# BNSK_Authoring_Light.net
KiCad netlist of a schematic drawn in EAGLE
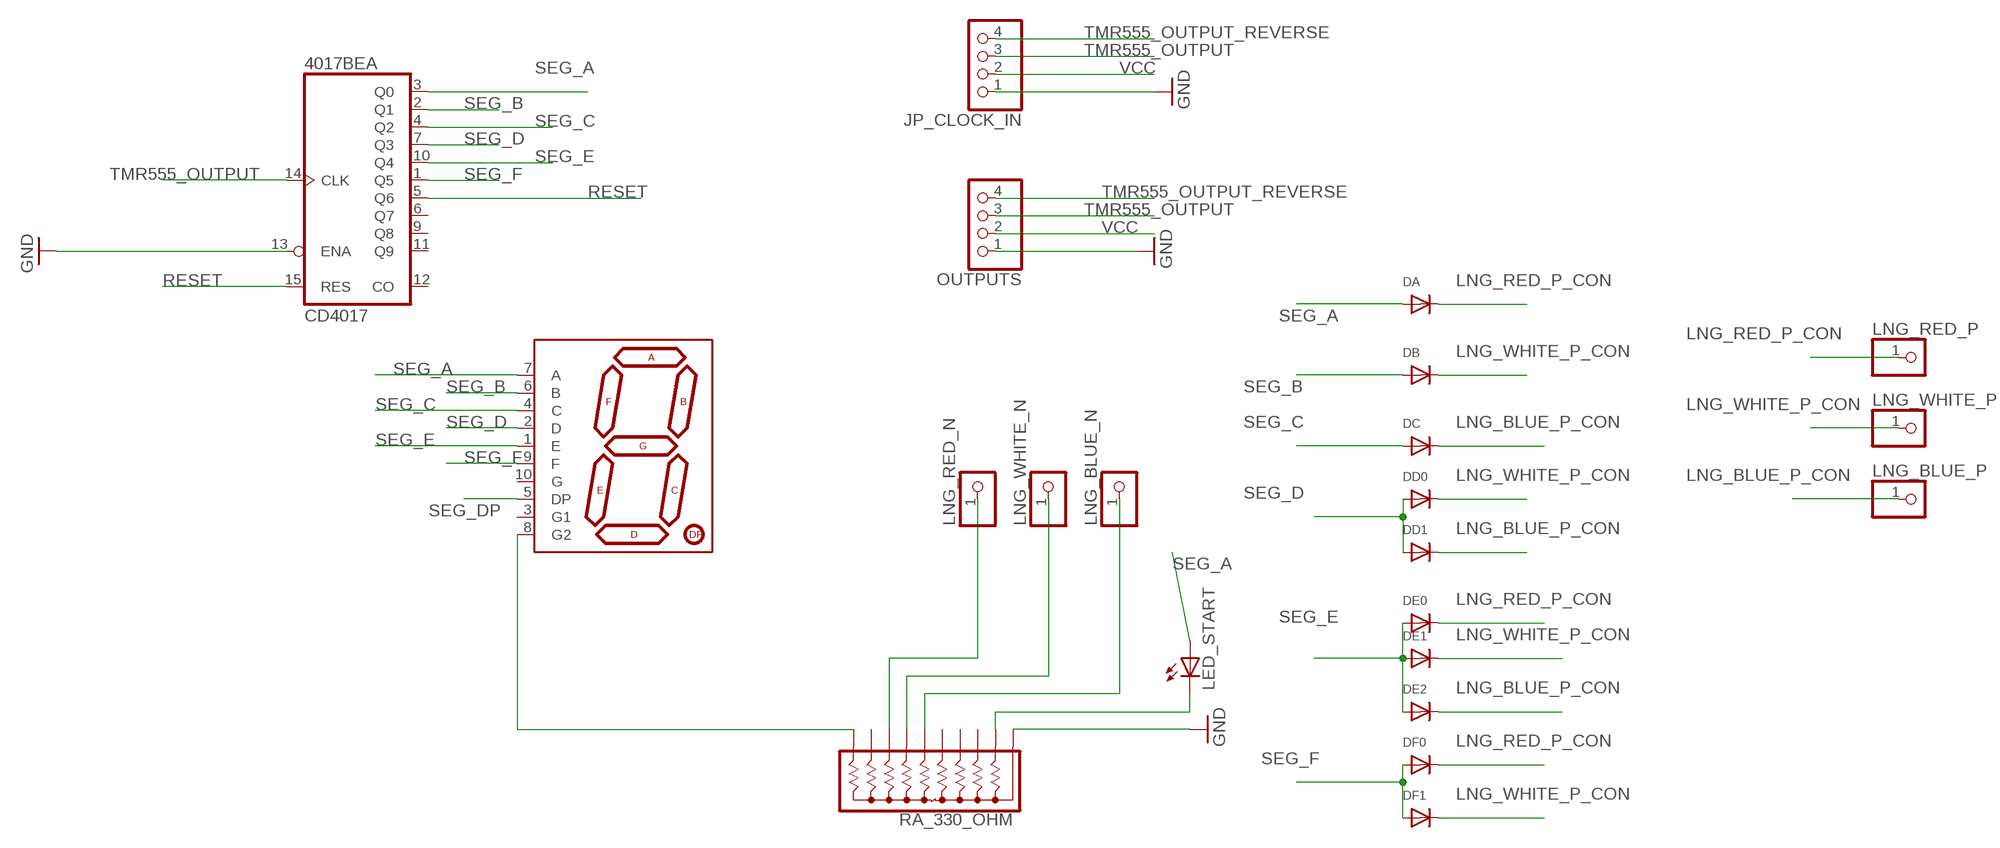
[diagram p0: schematic, sheet 1]

(export (version "E")
  (design (tool "Eeschema 10.0.6"))
  (components
    (comp (ref "4017BE")
      (value "CD4017")
      (footprint "eagle-import:DIL16")
      (libsource (lib "eagle-import") (part "CD4017"))
    )
    (comp (ref "DA")
      (value "DIODESMA")
      (footprint "eagle-import:SMADIODE")
      (libsource (lib "eagle-import") (part "DIODESMA"))
    )
    (comp (ref "DB")
      (value "DIODESMA")
      (footprint "eagle-import:SMADIODE")
      (libsource (lib "eagle-import") (part "DIODESMA"))
    )
    (comp (ref "DC")
      (value "DIODESMA")
      (footprint "eagle-import:SMADIODE")
      (libsource (lib "eagle-import") (part "DIODESMA"))
    )
    (comp (ref "DD0")
      (value "DIODESMA")
      (footprint "eagle-import:SMADIODE")
      (libsource (lib "eagle-import") (part "DIODESMA"))
    )
    (comp (ref "DD1")
      (value "DIODESMA")
      (footprint "eagle-import:SMADIODE")
      (libsource (lib "eagle-import") (part "DIODESMA"))
    )
    (comp (ref "DE0")
      (value "DIODESMA")
      (footprint "eagle-import:SMADIODE")
      (libsource (lib "eagle-import") (part "DIODESMA"))
    )
    (comp (ref "DE1")
      (value "DIODESMA")
      (footprint "eagle-import:SMADIODE")
      (libsource (lib "eagle-import") (part "DIODESMA"))
    )
    (comp (ref "DE2")
      (value "DIODESMA")
      (footprint "eagle-import:SMADIODE")
      (libsource (lib "eagle-import") (part "DIODESMA"))
    )
    (comp (ref "DF0")
      (value "DIODESMA")
      (footprint "eagle-import:SMADIODE")
      (libsource (lib "eagle-import") (part "DIODESMA"))
    )
    (comp (ref "DF1")
      (value "DIODESMA")
      (footprint "eagle-import:SMADIODE")
      (libsource (lib "eagle-import") (part "DIODESMA"))
    )
    (comp (ref "JP_CLOCK_IN")
      (value "PINHD-1X4")
      (footprint "eagle-import:1X04")
      (libsource (lib "eagle-import") (part "PINHD-1X4"))
    )
    (comp (ref "LED_START")
      (value "LEDSMT1206")
      (footprint "eagle-import:1206")
      (libsource (lib "eagle-import") (part "LEDSMT1206"))
    )
    (comp (ref "LNG_BLUE_N")
      (value "PINHD-1X1")
      (footprint "eagle-import:1X01")
      (libsource (lib "eagle-import") (part "PINHD-1X1"))
    )
    (comp (ref "LNG_BLUE_P")
      (value "PINHD-1X1")
      (footprint "eagle-import:1X01")
      (libsource (lib "eagle-import") (part "PINHD-1X1"))
    )
    (comp (ref "LNG_RED_N")
      (value "PINHD-1X1")
      (footprint "eagle-import:1X01")
      (libsource (lib "eagle-import") (part "PINHD-1X1"))
    )
    (comp (ref "LNG_RED_P")
      (value "PINHD-1X1")
      (footprint "eagle-import:1X01")
      (libsource (lib "eagle-import") (part "PINHD-1X1"))
    )
    (comp (ref "LNG_WHITE_N")
      (value "PINHD-1X1")
      (footprint "eagle-import:1X01")
      (libsource (lib "eagle-import") (part "PINHD-1X1"))
    )
    (comp (ref "LNG_WHITE_P")
      (value "PINHD-1X1")
      (footprint "eagle-import:1X01")
      (libsource (lib "eagle-import") (part "PINHD-1X1"))
    )
    (comp (ref "OUTPUTS")
      (value "PINHD-1X4")
      (footprint "eagle-import:1X04")
      (libsource (lib "eagle-import") (part "PINHD-1X4"))
    )
    (comp (ref "RA_330_OHM")
      (value "4610X")
      (footprint "eagle-import:SIP10")
      (libsource (lib "eagle-import") (part "4610X"))
    )
    (comp (ref "U$1")
      (value "7-SEGMENT-DISPLAYPTH")
      (footprint "eagle-import:7-SEGMENT-DISPLAY")
      (libsource (lib "eagle-import") (part "7-SEGMENT-DISPLAYPTH"))
    )
  )
  (nets
    (net (code "1") (name "/LNG_BLUE_P_CON") (class "Default")
      (node (ref "DC") (pin "C") (pinfunction "C_C") (pintype "passive"))
      (node (ref "DD1") (pin "C") (pinfunction "C_C") (pintype "passive"))
      (node (ref "DE2") (pin "C") (pinfunction "C_C") (pintype "passive"))
      (node (ref "LNG_BLUE_P") (pin "1") (pinfunction "1_1") (pintype "passive"))
    )
    (net (code "2") (name "/LNG_RED_P_CON") (class "Default")
      (node (ref "DA") (pin "C") (pinfunction "C_C") (pintype "passive"))
      (node (ref "DE0") (pin "C") (pinfunction "C_C") (pintype "passive"))
      (node (ref "DF0") (pin "C") (pinfunction "C_C") (pintype "passive"))
      (node (ref "LNG_RED_P") (pin "1") (pinfunction "1_1") (pintype "passive"))
    )
    (net (code "3") (name "/LNG_WHITE_P_CON") (class "Default")
      (node (ref "DB") (pin "C") (pinfunction "C_C") (pintype "passive"))
      (node (ref "DD0") (pin "C") (pinfunction "C_C") (pintype "passive"))
      (node (ref "DE1") (pin "C") (pinfunction "C_C") (pintype "passive"))
      (node (ref "DF1") (pin "C") (pinfunction "C_C") (pintype "passive"))
      (node (ref "LNG_WHITE_P") (pin "1") (pinfunction "1_1") (pintype "passive"))
    )
    (net (code "4") (name "/RESET") (class "Default")
      (node (ref "4017BE") (pin "15") (pinfunction "RES_15") (pintype "input"))
      (node (ref "4017BE") (pin "5") (pinfunction "Q6_5") (pintype "output"))
    )
    (net (code "5") (name "/SEG_A") (class "Default")
      (node (ref "4017BE") (pin "3") (pinfunction "Q0_3") (pintype "output"))
      (node (ref "DA") (pin "A") (pinfunction "A_A") (pintype "passive"))
      (node (ref "LED_START") (pin "A") (pinfunction "A_A") (pintype "passive"))
      (node (ref "U$1") (pin "7") (pinfunction "A_7") (pintype "bidirectional"))
    )
    (net (code "6") (name "/SEG_B") (class "Default")
      (node (ref "4017BE") (pin "2") (pinfunction "Q1_2") (pintype "output"))
      (node (ref "DB") (pin "A") (pinfunction "A_A") (pintype "passive"))
      (node (ref "U$1") (pin "6") (pinfunction "B_6") (pintype "bidirectional"))
    )
    (net (code "7") (name "/SEG_C") (class "Default")
      (node (ref "4017BE") (pin "4") (pinfunction "Q2_4") (pintype "output"))
      (node (ref "DC") (pin "A") (pinfunction "A_A") (pintype "passive"))
      (node (ref "U$1") (pin "4") (pinfunction "C_4") (pintype "bidirectional"))
    )
    (net (code "8") (name "/SEG_D") (class "Default")
      (node (ref "4017BE") (pin "7") (pinfunction "Q3_7") (pintype "output"))
      (node (ref "DD0") (pin "A") (pinfunction "A_A") (pintype "passive"))
      (node (ref "DD1") (pin "A") (pinfunction "A_A") (pintype "passive"))
      (node (ref "U$1") (pin "2") (pinfunction "D_2") (pintype "bidirectional"))
    )
    (net (code "9") (name "/SEG_DP") (class "Default")
      (node (ref "U$1") (pin "5") (pinfunction "DP_5") (pintype "bidirectional"))
    )
    (net (code "10") (name "/SEG_E") (class "Default")
      (node (ref "4017BE") (pin "10") (pinfunction "Q4_10") (pintype "output"))
      (node (ref "DE0") (pin "A") (pinfunction "A_A") (pintype "passive"))
      (node (ref "DE1") (pin "A") (pinfunction "A_A") (pintype "passive"))
      (node (ref "DE2") (pin "A") (pinfunction "A_A") (pintype "passive"))
      (node (ref "U$1") (pin "1") (pinfunction "E_1") (pintype "bidirectional"))
    )
    (net (code "11") (name "/SEG_F") (class "Default")
      (node (ref "4017BE") (pin "1") (pinfunction "Q5_1") (pintype "output"))
      (node (ref "DF0") (pin "A") (pinfunction "A_A") (pintype "passive"))
      (node (ref "DF1") (pin "A") (pinfunction "A_A") (pintype "passive"))
      (node (ref "U$1") (pin "9") (pinfunction "F_9") (pintype "bidirectional"))
    )
    (net (code "12") (name "/TMR555_OUTPUT") (class "Default")
      (node (ref "4017BE") (pin "14") (pinfunction "CLK_14") (pintype "input"))
      (node (ref "JP_CLOCK_IN") (pin "3") (pinfunction "3_3") (pintype "passive"))
      (node (ref "OUTPUTS") (pin "3") (pinfunction "3_3") (pintype "passive"))
    )
    (net (code "13") (name "/TMR555_OUTPUT_REVERSE") (class "Default")
      (node (ref "JP_CLOCK_IN") (pin "4") (pinfunction "4_4") (pintype "passive"))
      (node (ref "OUTPUTS") (pin "4") (pinfunction "4_4") (pintype "passive"))
    )
    (net (code "14") (name "/VCC") (class "Default")
      (node (ref "JP_CLOCK_IN") (pin "2") (pinfunction "2_2") (pintype "passive"))
      (node (ref "OUTPUTS") (pin "2") (pinfunction "2_2") (pintype "passive"))
    )
    (net (code "15") (name "GND") (class "Default")
      (node (ref "4017BE") (pin "13") (pinfunction "ENA_13") (pintype "input"))
      (node (ref "JP_CLOCK_IN") (pin "1") (pinfunction "1_1") (pintype "passive"))
      (node (ref "OUTPUTS") (pin "1") (pinfunction "1_1") (pintype "passive"))
      (node (ref "RA_330_OHM") (pin "1") (pinfunction "1_1") (pintype "passive"))
    )
    (net (code "16") (name "Net-(LED_START-PadC)") (class "Default")
      (node (ref "LED_START") (pin "C") (pinfunction "C_C") (pintype "passive"))
      (node (ref "RA_330_OHM") (pin "2") (pinfunction "2_2") (pintype "passive"))
    )
    (net (code "17") (name "Net-(LNG_BLUE_N-Pad1)") (class "Default")
      (node (ref "LNG_BLUE_N") (pin "1") (pinfunction "1_1") (pintype "passive"))
      (node (ref "RA_330_OHM") (pin "6") (pinfunction "6_6") (pintype "passive"))
    )
    (net (code "18") (name "Net-(LNG_RED_N-Pad1)") (class "Default")
      (node (ref "LNG_RED_N") (pin "1") (pinfunction "1_1") (pintype "passive"))
      (node (ref "RA_330_OHM") (pin "8") (pinfunction "8_8") (pintype "passive"))
    )
    (net (code "19") (name "Net-(LNG_WHITE_N-Pad1)") (class "Default")
      (node (ref "LNG_WHITE_N") (pin "1") (pinfunction "1_1") (pintype "passive"))
      (node (ref "RA_330_OHM") (pin "7") (pinfunction "7_7") (pintype "passive"))
    )
    (net (code "20") (name "Net-(U$1-G2)") (class "Default")
      (node (ref "RA_330_OHM") (pin "10") (pinfunction "10_10") (pintype "passive"))
      (node (ref "U$1") (pin "8") (pinfunction "G2_8") (pintype "bidirectional"))
    )
    (net (code "21") (name "unconnected-(4017BEA-CO-Pad12)") (class "Default")
      (node (ref "4017BE") (pin "12") (pinfunction "CO_12") (pintype "output"))
    )
    (net (code "22") (name "unconnected-(4017BEA-Q7-Pad6)") (class "Default")
      (node (ref "4017BE") (pin "6") (pinfunction "Q7_6") (pintype "output"))
    )
    (net (code "23") (name "unconnected-(4017BEA-Q8-Pad9)") (class "Default")
      (node (ref "4017BE") (pin "9") (pinfunction "Q8_9") (pintype "output"))
    )
    (net (code "24") (name "unconnected-(4017BEA-Q9-Pad11)") (class "Default")
      (node (ref "4017BE") (pin "11") (pinfunction "Q9_11") (pintype "output"))
    )
    (net (code "25") (name "unconnected-(RA_330_OHM-Pad3)") (class "Default")
      (node (ref "RA_330_OHM") (pin "3") (pinfunction "3_3") (pintype "passive"))
    )
    (net (code "26") (name "unconnected-(RA_330_OHM-Pad4)") (class "Default")
      (node (ref "RA_330_OHM") (pin "4") (pinfunction "4_4") (pintype "passive"))
    )
    (net (code "27") (name "unconnected-(RA_330_OHM-Pad5)") (class "Default")
      (node (ref "RA_330_OHM") (pin "5") (pinfunction "5_5") (pintype "passive"))
    )
    (net (code "28") (name "unconnected-(RA_330_OHM-Pad9)") (class "Default")
      (node (ref "RA_330_OHM") (pin "9") (pinfunction "9_9") (pintype "passive"))
    )
    (net (code "29") (name "unconnected-(U$1-G-Pad10)") (class "Default")
      (node (ref "U$1") (pin "10") (pinfunction "G_10") (pintype "bidirectional"))
    )
    (net (code "30") (name "unconnected-(U$1-G1-Pad3)") (class "Default")
      (node (ref "U$1") (pin "3") (pinfunction "G1_3") (pintype "bidirectional"))
    )
  )
)
